# panel_IO.net
KiCad netlist of a schematic drawn in Altium Designer
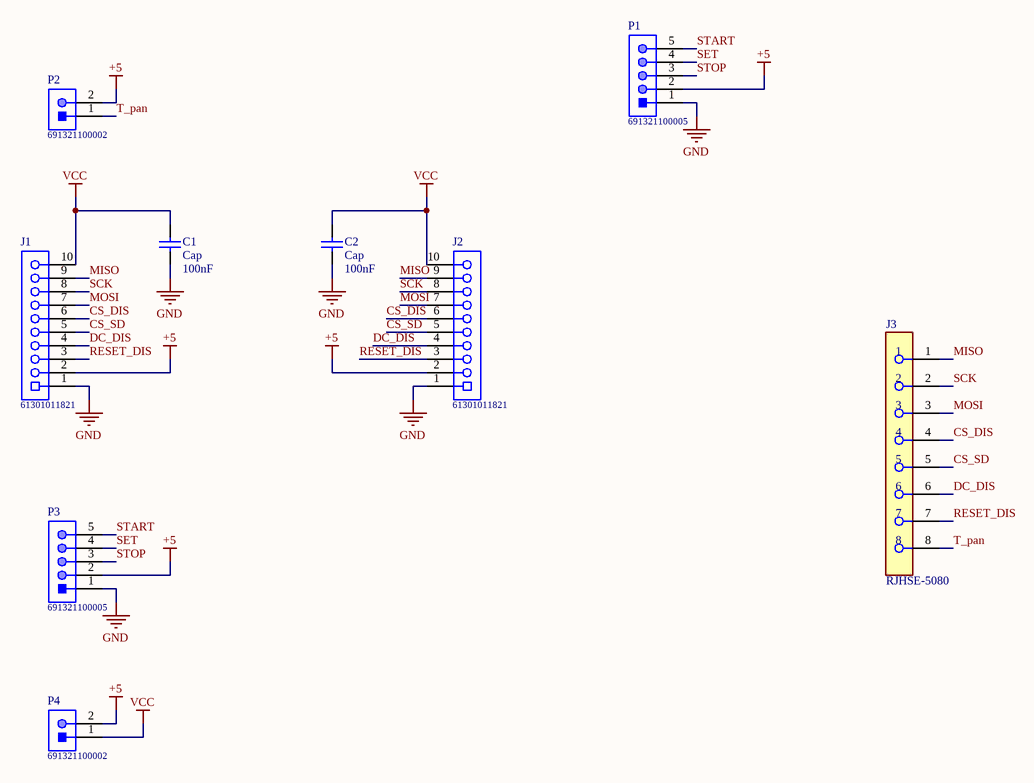
[diagram p0: panel_IO.SchDoc]

(export (version "E")
  (design (tool "Eeschema 10.0.6"))
  (components
    (comp (ref "C1")
      (value "Cap")
      (footprint "RAD-0.3")
      (description "Capacitor")
      (fields (field (name "ALTIUM_VALUE") "100nF") (field (name "PUBLISHER") "Altium Limited"))
      (libsource (lib "Miscellaneous Devices") (part "Cap"))
    )
    (comp (ref "C2")
      (value "Cap")
      (footprint "RAD-0.3")
      (description "Capacitor")
      (fields (field (name "ALTIUM_VALUE") "100nF") (field (name "PUBLISHER") "Altium Limited"))
      (libsource (lib "Miscellaneous Devices") (part "Cap"))
    )
    (comp (ref "J1")
      (value "61301011821")
      (footprint "61301011821")
      (description "THT Vertical Socket Header WR-PHD, Pitch 2.54 mm, Single Row, 10 pins")
      (fields (field (name "MANUFACTURER") "Wurth Elektronik") (field (name "PUBLISHER") "WurthElektronik"))
      (libsource (lib "Altium Content Vault") (part "WE-CN-1P-F-R10"))
    )
    (comp (ref "J2")
      (value "61301011821")
      (footprint "61301011821")
      (description "THT Vertical Socket Header WR-PHD, Pitch 2.54 mm, Single Row, 10 pins")
      (fields (field (name "MANUFACTURER") "Wurth Elektronik") (field (name "PUBLISHER") "WurthElektronik"))
      (libsource (lib "") (part "WE-CN-1P-F-R10_1"))
    )
    (comp (ref "J3")
      (value "RJHSE-5080")
      (footprint "FP-RJHSE-5080-MFG")
      (description "CONN MOD JACK 8P8C R/A UNSHLD")
      (fields
        (field (name "OCTOPART") "https://octopart.com/rjhse-5080-amphenol-45060")
        (field (name "MANUFACTURER") "Amphenol")
      )
      (libsource (lib "Altium Content Vault") (part "b0a0b555dd3abf3683e7c330df25cc4"))
    )
    (comp (ref "P1")
      (value "691321100005")
      (footprint "691321100005")
      (description "Serie 3211 - 3.50mm Vertical PCB Header WR-TBL, 5 pin")
      (fields (field (name "MANUFACTURER") "Wurth Elektronik") (field (name "PUBLISHER") "WurthElektronik"))
      (libsource (lib "Altium Content Vault") (part "WE-CN-1P-M-R5"))
    )
    (comp (ref "P2")
      (value "691321100002")
      (footprint "691321100002")
      (description "Serie 3211 - 3.50mm Vertical PCB Header WR-TBL, 2 pin")
      (fields (field (name "MANUFACTURER") "Wurth Elektronik") (field (name "PUBLISHER") "WurthElektronik"))
      (libsource (lib "Altium Content Vault") (part "WE-CN-1P-M-R2"))
    )
    (comp (ref "P3")
      (value "691321100005")
      (footprint "691321100005")
      (description "Serie 3211 - 3.50mm Vertical PCB Header WR-TBL, 5 pin")
      (fields (field (name "MANUFACTURER") "Wurth Elektronik") (field (name "PUBLISHER") "WurthElektronik"))
      (libsource (lib "Altium Content Vault") (part "WE-CN-1P-M-R5"))
    )
    (comp (ref "P4")
      (value "691321100002")
      (footprint "691321100002")
      (description "Serie 3211 - 3.50mm Vertical PCB Header WR-TBL, 2 pin")
      (fields (field (name "MANUFACTURER") "Wurth Elektronik") (field (name "PUBLISHER") "WurthElektronik"))
      (libsource (lib "Altium Content Vault") (part "WE-CN-1P-M-R2"))
    )
  )
  (nets
    (net (code "1") (name "+5") (class "Default")
      (node (ref "J1") (pin "2") (pinfunction "2_2") (pintype "passive"))
      (node (ref "J2") (pin "2") (pinfunction "2_2") (pintype "passive"))
      (node (ref "P1") (pin "2") (pinfunction "2_2") (pintype "passive"))
      (node (ref "P2") (pin "2") (pinfunction "2_2") (pintype "passive"))
      (node (ref "P3") (pin "2") (pinfunction "2_2") (pintype "passive"))
      (node (ref "P4") (pin "2") (pinfunction "2_2") (pintype "passive"))
    )
    (net (code "2") (name "/CS_DIS") (class "Default")
      (node (ref "J1") (pin "6") (pinfunction "6_6") (pintype "passive"))
      (node (ref "J2") (pin "6") (pinfunction "6_6") (pintype "passive"))
      (node (ref "J3") (pin "4") (pinfunction "4_4") (pintype "passive"))
    )
    (net (code "3") (name "/CS_SD") (class "Default")
      (node (ref "J1") (pin "5") (pinfunction "5_5") (pintype "passive"))
      (node (ref "J2") (pin "5") (pinfunction "5_5") (pintype "passive"))
      (node (ref "J3") (pin "5") (pinfunction "5_5") (pintype "passive"))
    )
    (net (code "4") (name "/DC_DIS") (class "Default")
      (node (ref "J1") (pin "4") (pinfunction "4_4") (pintype "passive"))
      (node (ref "J2") (pin "4") (pinfunction "4_4") (pintype "passive"))
      (node (ref "J3") (pin "6") (pinfunction "6_6") (pintype "passive"))
    )
    (net (code "5") (name "/MISO") (class "Default")
      (node (ref "J1") (pin "9") (pinfunction "9_9") (pintype "passive"))
      (node (ref "J2") (pin "9") (pinfunction "9_9") (pintype "passive"))
      (node (ref "J3") (pin "1") (pinfunction "1_1") (pintype "passive"))
    )
    (net (code "6") (name "/MOSI") (class "Default")
      (node (ref "J1") (pin "7") (pinfunction "7_7") (pintype "passive"))
      (node (ref "J2") (pin "7") (pinfunction "7_7") (pintype "passive"))
      (node (ref "J3") (pin "3") (pinfunction "3_3") (pintype "passive"))
    )
    (net (code "7") (name "/RESET_DIS") (class "Default")
      (node (ref "J1") (pin "3") (pinfunction "3_3") (pintype "passive"))
      (node (ref "J2") (pin "3") (pinfunction "3_3") (pintype "passive"))
      (node (ref "J3") (pin "7") (pinfunction "7_7") (pintype "passive"))
    )
    (net (code "8") (name "/SCK") (class "Default")
      (node (ref "J1") (pin "8") (pinfunction "8_8") (pintype "passive"))
      (node (ref "J2") (pin "8") (pinfunction "8_8") (pintype "passive"))
      (node (ref "J3") (pin "2") (pinfunction "2_2") (pintype "passive"))
    )
    (net (code "9") (name "/SET") (class "Default")
      (node (ref "P1") (pin "4") (pinfunction "4_4") (pintype "passive"))
      (node (ref "P3") (pin "4") (pinfunction "4_4") (pintype "passive"))
    )
    (net (code "10") (name "/START") (class "Default")
      (node (ref "P1") (pin "5") (pinfunction "5_5") (pintype "passive"))
      (node (ref "P3") (pin "5") (pinfunction "5_5") (pintype "passive"))
    )
    (net (code "11") (name "/STOP") (class "Default")
      (node (ref "P1") (pin "3") (pinfunction "3_3") (pintype "passive"))
      (node (ref "P3") (pin "3") (pinfunction "3_3") (pintype "passive"))
    )
    (net (code "12") (name "/T_pan") (class "Default")
      (node (ref "J3") (pin "8") (pinfunction "8_8") (pintype "passive"))
      (node (ref "P2") (pin "1") (pinfunction "1_1") (pintype "passive"))
    )
    (net (code "13") (name "GND") (class "Default")
      (node (ref "C1") (pin "1") (pinfunction "1_1") (pintype "passive"))
      (node (ref "C2") (pin "1") (pinfunction "1_1") (pintype "passive"))
      (node (ref "J1") (pin "1") (pinfunction "1_1") (pintype "passive"))
      (node (ref "J2") (pin "1") (pinfunction "1_1") (pintype "passive"))
      (node (ref "P1") (pin "1") (pinfunction "1_1") (pintype "passive"))
      (node (ref "P3") (pin "1") (pinfunction "1_1") (pintype "passive"))
    )
    (net (code "14") (name "VCC") (class "Default")
      (node (ref "C1") (pin "2") (pinfunction "2_2") (pintype "passive"))
      (node (ref "C2") (pin "2") (pinfunction "2_2") (pintype "passive"))
      (node (ref "J1") (pin "10") (pinfunction "10_10") (pintype "passive"))
      (node (ref "J2") (pin "10") (pinfunction "10_10") (pintype "passive"))
      (node (ref "P4") (pin "1") (pinfunction "1_1") (pintype "passive"))
    )
  )
)
